# MTRduino_rev5_0.net
KiCad netlist of a schematic drawn in EAGLE
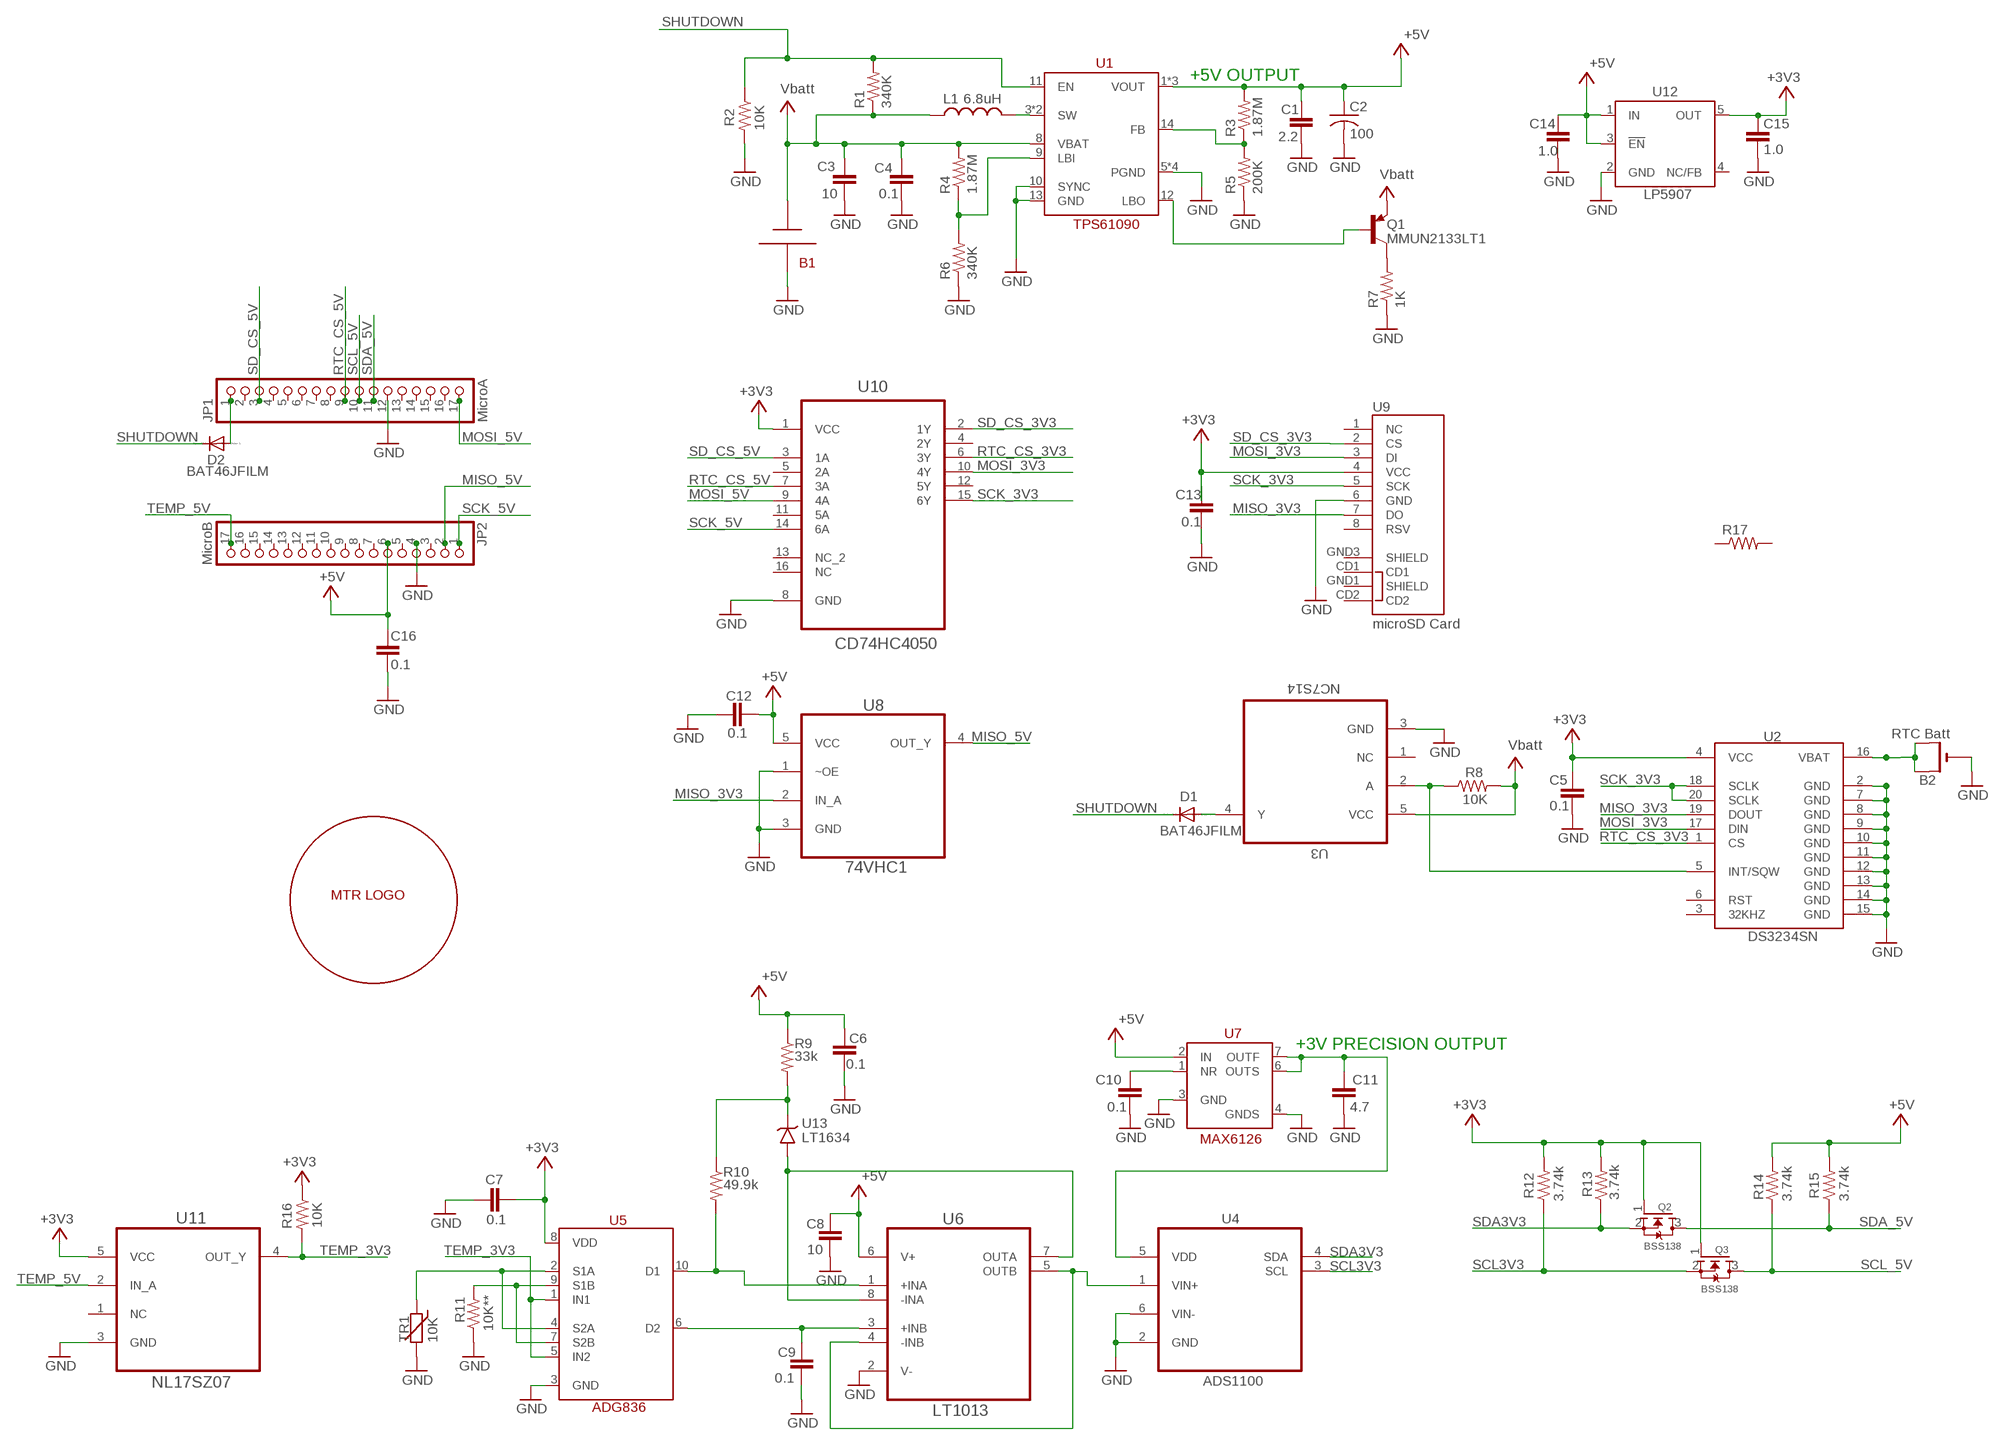
[diagram p0: schematic, sheet 1]

(export (version "E")
  (design (tool "Eeschema 10.0.6"))
  (components
    (comp (ref "B1")
      (value "2x AA BATT")
      (footprint "eagle-import:BATT_AA2")
      (libsource (lib "eagle-import") (part "BATT_AA2"))
    )
    (comp (ref "B2")
      (value "RTC Batt")
      (footprint "eagle-import:CR1220-SMD")
      (libsource (lib "eagle-import") (part "CR1220SMT"))
    )
    (comp (ref "C1")
      (value "2.2")
      (footprint "eagle-import:C0603")
      (libsource (lib "eagle-import") (part "C-EUC0603"))
    )
    (comp (ref "C2")
      (value "100")
      (footprint "eagle-import:C1206K")
      (libsource (lib "eagle-import") (part "C-USC1206K"))
    )
    (comp (ref "C3")
      (value "10")
      (footprint "eagle-import:C0603")
      (libsource (lib "eagle-import") (part "C-EUC0603"))
    )
    (comp (ref "C4")
      (value "0.1")
      (footprint "eagle-import:C0603")
      (libsource (lib "eagle-import") (part "C-EUC0603"))
    )
    (comp (ref "C5")
      (value "0.1")
      (footprint "eagle-import:C0603")
      (libsource (lib "eagle-import") (part "C-EUC0603"))
    )
    (comp (ref "C6")
      (value "0.1")
      (footprint "eagle-import:C0603")
      (libsource (lib "eagle-import") (part "C-EUC0603"))
    )
    (comp (ref "C7")
      (value "0.1")
      (footprint "eagle-import:C0603")
      (libsource (lib "eagle-import") (part "C-EUC0603"))
    )
    (comp (ref "C8")
      (value "10")
      (footprint "eagle-import:C0603")
      (libsource (lib "eagle-import") (part "C-EUC0603"))
    )
    (comp (ref "C9")
      (value "0.1")
      (footprint "eagle-import:C0603")
      (libsource (lib "eagle-import") (part "C-EUC0603"))
    )
    (comp (ref "C10")
      (value "0.1")
      (footprint "eagle-import:C0603")
      (libsource (lib "eagle-import") (part "C-EUC0603"))
    )
    (comp (ref "C11")
      (value "4.7")
      (footprint "eagle-import:C0603")
      (libsource (lib "eagle-import") (part "C-EUC0603"))
    )
    (comp (ref "C12")
      (value "0.1")
      (footprint "eagle-import:C0603")
      (libsource (lib "eagle-import") (part "C-EUC0603"))
    )
    (comp (ref "C13")
      (value "0.1")
      (footprint "eagle-import:C0603")
      (libsource (lib "eagle-import") (part "C-EUC0603"))
    )
    (comp (ref "C14")
      (value "1.0")
      (footprint "eagle-import:C0603")
      (libsource (lib "eagle-import") (part "C-EUC0603"))
    )
    (comp (ref "C15")
      (value "1.0")
      (footprint "eagle-import:C0603")
      (libsource (lib "eagle-import") (part "C-EUC0603"))
    )
    (comp (ref "C16")
      (value "0.1")
      (footprint "eagle-import:C0603")
      (libsource (lib "eagle-import") (part "C-EUC0603"))
    )
    (comp (ref "D1")
      (value "BAT46JFILM")
      (footprint "eagle-import:SOD323-R")
      (libsource (lib "eagle-import") (part "DIODE-SOD323-R"))
    )
    (comp (ref "D2")
      (value "BAT46JFILM")
      (footprint "eagle-import:SOD323-R")
      (libsource (lib "eagle-import") (part "DIODE-SOD323-R"))
    )
    (comp (ref "JP1")
      (value "MicroA")
      (footprint "eagle-import:1X17")
      (libsource (lib "eagle-import") (part "PINHD-1X17"))
    )
    (comp (ref "JP2")
      (value "MicroB")
      (footprint "eagle-import:1X17")
      (libsource (lib "eagle-import") (part "PINHD-1X17"))
    )
    (comp (ref "L1")
      (value "6.8uH")
      (footprint "eagle-import:VLC6045")
      (libsource (lib "eagle-import") (part "L-USVLC6045"))
    )
    (comp (ref "Q1")
      (value "MMUN2133LT1")
      (footprint "eagle-import:SC59-BEC")
      (libsource (lib "eagle-import") (part "MMUN2111LT1"))
    )
    (comp (ref "Q2")
      (value "BSS138")
      (footprint "eagle-import:SOT23")
      (libsource (lib "eagle-import") (part "MOSFET-NREFLOW"))
    )
    (comp (ref "Q3")
      (value "BSS138")
      (footprint "eagle-import:SOT23")
      (libsource (lib "eagle-import") (part "MOSFET-NREFLOW"))
    )
    (comp (ref "R1")
      (value "340K")
      (footprint "eagle-import:R0603")
      (libsource (lib "eagle-import") (part "resistor_R-US_R0603"))
    )
    (comp (ref "R2")
      (value "10K")
      (footprint "eagle-import:R0603")
      (libsource (lib "eagle-import") (part "resistor_R-US_R0603"))
    )
    (comp (ref "R3")
      (value "1.87M")
      (footprint "eagle-import:R0805")
      (libsource (lib "eagle-import") (part "resistor_R-US_R0805"))
    )
    (comp (ref "R4")
      (value "1.87M")
      (footprint "eagle-import:R0805")
      (libsource (lib "eagle-import") (part "resistor_R-US_R0805"))
    )
    (comp (ref "R5")
      (value "200K")
      (footprint "eagle-import:R0603")
      (libsource (lib "eagle-import") (part "resistor_R-US_R0603"))
    )
    (comp (ref "R6")
      (value "340K")
      (footprint "eagle-import:R0603")
      (libsource (lib "eagle-import") (part "resistor_R-US_R0603"))
    )
    (comp (ref "R7")
      (value "1K")
      (footprint "eagle-import:R0603")
      (libsource (lib "eagle-import") (part "resistor_R-US_R0603"))
    )
    (comp (ref "R8")
      (value "10K")
      (footprint "eagle-import:R0603")
      (libsource (lib "eagle-import") (part "resistor_R-US_R0603"))
    )
    (comp (ref "R9")
      (value "33k")
      (footprint "eagle-import:R0603")
      (libsource (lib "eagle-import") (part "resistor_R-US_R0603"))
    )
    (comp (ref "R10")
      (value "49.9k")
      (footprint "eagle-import:R0603")
      (libsource (lib "eagle-import") (part "resistor_R-US_R0603"))
    )
    (comp (ref "R11")
      (value "10K**")
      (footprint "eagle-import:R1206")
      (libsource (lib "eagle-import") (part "R-US_R1206"))
    )
    (comp (ref "R12")
      (value "3.74k")
      (footprint "eagle-import:R0603")
      (libsource (lib "eagle-import") (part "resistor_R-US_R0603"))
    )
    (comp (ref "R13")
      (value "3.74k")
      (footprint "eagle-import:R0603")
      (libsource (lib "eagle-import") (part "resistor_R-US_R0603"))
    )
    (comp (ref "R14")
      (value "3.74k")
      (footprint "eagle-import:R0603")
      (libsource (lib "eagle-import") (part "resistor_R-US_R0603"))
    )
    (comp (ref "R15")
      (value "3.74k")
      (footprint "eagle-import:R0603")
      (libsource (lib "eagle-import") (part "resistor_R-US_R0603"))
    )
    (comp (ref "R16")
      (value "10K")
      (footprint "eagle-import:R0603")
      (libsource (lib "eagle-import") (part "resistor_R-US_R0603"))
    )
    (comp (ref "R17")
      (value "R-US_R0805")
      (footprint "eagle-import:R0805")
      (libsource (lib "eagle-import") (part "resistor_R-US_R0805"))
    )
    (comp (ref "TR1")
      (value "10K")
      (footprint "eagle-import:R-5")
      (libsource (lib "eagle-import") (part "THERMISTOR_R-5"))
    )
    (comp (ref "U$1")
      (value "MTRLOGO")
      (footprint "eagle-import:MTRLOGO")
      (libsource (lib "eagle-import") (part "MTRLOGO"))
    )
    (comp (ref "U1")
      (value "TPS61090")
      (footprint "eagle-import:QFN16-4X4")
      (libsource (lib "eagle-import") (part "TPS61090RSAR"))
    )
    (comp (ref "U2")
      (value "DS3234SN")
      (footprint "eagle-import:DS3234")
      (libsource (lib "eagle-import") (part "DS3234"))
    )
    (comp (ref "U3")
      (value "NC7S14")
      (footprint "eagle-import:SOT95P280X145-5N")
      (fields (field (name "MPN") "1P1G14MDBVREPG4"))
      (libsource (lib "eagle-import") (part "1P1G14MDBVREPG4"))
    )
    (comp (ref "U4")
      (value "ADS1100")
      (footprint "eagle-import:SOT95P280X145-6N")
      (fields (field (name "MPN") "ADS1100A0IDBVT"))
      (libsource (lib "eagle-import") (part "ADS1100A0IDBVT"))
    )
    (comp (ref "U5")
      (value "ADG836")
      (footprint "eagle-import:MSOP10")
      (libsource (lib "eagle-import") (part "ADG836"))
    )
    (comp (ref "U6")
      (value "LT1013")
      (footprint "eagle-import:SOIC127P600X175-8N")
      (fields (field (name "MPN") "LT1013DS8#PBF"))
      (libsource (lib "eagle-import") (part "LT1013DS8PBF"))
    )
    (comp (ref "U7")
      (value "MAX6126")
      (footprint "eagle-import:SOIC127P600X175-8N")
      (libsource (lib "eagle-import") (part "MAX6126"))
    )
    (comp (ref "U8")
      (value "74VHC1")
      (footprint "eagle-import:SOT65P210X110-5N")
      (fields (field (name "MPN") "M74VHC1GT125DF1G"))
      (libsource (lib "eagle-import") (part "M74VHC1GT125DF1G"))
    )
    (comp (ref "U9")
      (value "microSD Card")
      (footprint "eagle-import:MICROSD_1_1")
      (libsource (lib "eagle-import") (part "USD-SOCKET"))
    )
    (comp (ref "U10")
      (value "CD74HC4050")
      (footprint "eagle-import:SOIC127P600X175-16N")
      (fields (field (name "MPN") "M74HC4050RM13TR"))
      (libsource (lib "eagle-import") (part "M74HC4050RM13TR"))
    )
    (comp (ref "U11")
      (value "NL17SZ07")
      (footprint "eagle-import:SOT65P210X110-5N")
      (fields (field (name "MPN") "NL17SZ07DFT2G"))
      (libsource (lib "eagle-import") (part "NL17SZ07DFT2G"))
    )
    (comp (ref "U12")
      (value "LP5907")
      (footprint "eagle-import:SOT23-DBV")
      (fields (field (name "MF") "TEXAS INSTRUMENTS") (field (name "MPN") "TPS77030DBVT"))
      (libsource (lib "eagle-import") (part "TPS77030"))
    )
    (comp (ref "U13")
      (value "LT1634")
      (footprint "eagle-import:S8")
      (libsource (lib "eagle-import") (part "LT1634BIS8-1.25"))
    )
  )
  (nets
    (net (code "1") (name "+3V3") (class "Default")
      (node (ref "C13") (pin "1") (pinfunction "1_1") (pintype "passive"))
      (node (ref "C15") (pin "1") (pinfunction "1_1") (pintype "passive"))
      (node (ref "C5") (pin "1") (pinfunction "1_1") (pintype "passive"))
      (node (ref "C7") (pin "2") (pinfunction "2_2") (pintype "passive"))
      (node (ref "Q2") (pin "1") (pinfunction "G_1") (pintype "bidirectional"))
      (node (ref "Q3") (pin "1") (pinfunction "G_1") (pintype "bidirectional"))
      (node (ref "R12") (pin "2") (pinfunction "2_2") (pintype "passive"))
      (node (ref "R13") (pin "2") (pinfunction "2_2") (pintype "passive"))
      (node (ref "R16") (pin "1") (pinfunction "1_1") (pintype "passive"))
      (node (ref "U10") (pin "1") (pinfunction "VCC_1") (pintype "power_in"))
      (node (ref "U11") (pin "5") (pinfunction "VCC_5") (pintype "power_in"))
      (node (ref "U12") (pin "5") (pinfunction "OUT_5") (pintype "passive"))
      (node (ref "U2") (pin "4") (pinfunction "VCC_4") (pintype "bidirectional"))
      (node (ref "U5") (pin "8") (pinfunction "VDD_8") (pintype "bidirectional"))
      (node (ref "U9") (pin "4") (pinfunction "VCC_4") (pintype "bidirectional"))
    )
    (net (code "2") (name "+5V") (class "Default")
      (node (ref "C1") (pin "1") (pinfunction "1_1") (pintype "passive"))
      (node (ref "C12") (pin "1") (pinfunction "1_1") (pintype "passive"))
      (node (ref "C14") (pin "1") (pinfunction "1_1") (pintype "passive"))
      (node (ref "C16") (pin "1") (pinfunction "1_1") (pintype "passive"))
      (node (ref "C2") (pin "1") (pinfunction "1_1") (pintype "passive"))
      (node (ref "C6") (pin "2") (pinfunction "2_2") (pintype "passive"))
      (node (ref "C8") (pin "2") (pinfunction "2_2") (pintype "passive"))
      (node (ref "JP2") (pin "6") (pinfunction "6_6") (pintype "passive"))
      (node (ref "R14") (pin "2") (pinfunction "2_2") (pintype "passive"))
      (node (ref "R15") (pin "2") (pinfunction "2_2") (pintype "passive"))
      (node (ref "R3") (pin "2") (pinfunction "2_2") (pintype "passive"))
      (node (ref "R9") (pin "1") (pinfunction "1_1") (pintype "passive"))
      (node (ref "U1") (pin "1") (pinfunction "VOUT_1") (pintype "bidirectional"))
      (node (ref "U1") (pin "15") (pinfunction "VOUT_15") (pintype "bidirectional"))
      (node (ref "U1") (pin "16") (pinfunction "VOUT_16") (pintype "bidirectional"))
      (node (ref "U12") (pin "1") (pinfunction "IN_1") (pintype "input"))
      (node (ref "U12") (pin "3") (pinfunction "~{EN}_3") (pintype "input"))
      (node (ref "U6") (pin "6") (pinfunction "V+_6") (pintype "power_in"))
      (node (ref "U7") (pin "2") (pinfunction "IN_2") (pintype "input"))
      (node (ref "U8") (pin "5") (pinfunction "VCC_5") (pintype "power_in"))
    )
    (net (code "3") (name "/MISO_3V3") (class "Default")
      (node (ref "U2") (pin "19") (pinfunction "DOUT_19") (pintype "bidirectional"))
      (node (ref "U8") (pin "2") (pinfunction "IN_A_2") (pintype "input"))
      (node (ref "U9") (pin "7") (pinfunction "DO_7") (pintype "bidirectional"))
    )
    (net (code "4") (name "/MISO_5V") (class "Default")
      (node (ref "JP2") (pin "2") (pinfunction "2_2") (pintype "passive"))
      (node (ref "U8") (pin "4") (pinfunction "OUT_Y_4") (pintype "output"))
    )
    (net (code "5") (name "/MOSI_3V3") (class "Default")
      (node (ref "U10") (pin "10") (pinfunction "4Y_10") (pintype "output"))
      (node (ref "U2") (pin "17") (pinfunction "DIN_17") (pintype "bidirectional"))
      (node (ref "U9") (pin "3") (pinfunction "DI_3") (pintype "bidirectional"))
    )
    (net (code "6") (name "/MOSI_5V") (class "Default")
      (node (ref "JP1") (pin "17") (pinfunction "17_17") (pintype "passive"))
      (node (ref "U10") (pin "9") (pinfunction "4A_9") (pintype "input"))
    )
    (net (code "7") (name "/RTC_CS_3V3") (class "Default")
      (node (ref "U10") (pin "6") (pinfunction "3Y_6") (pintype "output"))
      (node (ref "U2") (pin "1") (pinfunction "CS_1") (pintype "bidirectional"))
    )
    (net (code "8") (name "/RTC_CS_5V") (class "Default")
      (node (ref "JP1") (pin "9") (pinfunction "9_9") (pintype "passive"))
      (node (ref "U10") (pin "7") (pinfunction "3A_7") (pintype "input"))
    )
    (net (code "9") (name "/SCK_3V3") (class "Default")
      (node (ref "U10") (pin "15") (pinfunction "6Y_15") (pintype "output"))
      (node (ref "U2") (pin "18") (pinfunction "SCLK_18") (pintype "bidirectional"))
      (node (ref "U2") (pin "20") (pinfunction "SCLK_20") (pintype "bidirectional"))
      (node (ref "U9") (pin "5") (pinfunction "SCK_5") (pintype "bidirectional"))
    )
    (net (code "10") (name "/SCK_5V") (class "Default")
      (node (ref "JP2") (pin "1") (pinfunction "1_1") (pintype "passive"))
      (node (ref "U10") (pin "14") (pinfunction "6A_14") (pintype "input"))
    )
    (net (code "11") (name "/SCL3V3") (class "Default")
      (node (ref "Q3") (pin "2") (pinfunction "S_2") (pintype "bidirectional"))
      (node (ref "R12") (pin "1") (pinfunction "1_1") (pintype "passive"))
      (node (ref "U4") (pin "3") (pinfunction "SCL_3") (pintype "output"))
    )
    (net (code "12") (name "/SCL_5V") (class "Default")
      (node (ref "JP1") (pin "10") (pinfunction "10_10") (pintype "passive"))
      (node (ref "Q3") (pin "3") (pinfunction "D_3") (pintype "bidirectional"))
      (node (ref "R14") (pin "1") (pinfunction "1_1") (pintype "passive"))
    )
    (net (code "13") (name "/SDA3V3") (class "Default")
      (node (ref "Q2") (pin "2") (pinfunction "S_2") (pintype "bidirectional"))
      (node (ref "R13") (pin "1") (pinfunction "1_1") (pintype "passive"))
      (node (ref "U4") (pin "4") (pinfunction "SDA_4") (pintype "output"))
    )
    (net (code "14") (name "/SDA_5V") (class "Default")
      (node (ref "JP1") (pin "11") (pinfunction "11_11") (pintype "passive"))
      (node (ref "Q2") (pin "3") (pinfunction "D_3") (pintype "bidirectional"))
      (node (ref "R15") (pin "1") (pinfunction "1_1") (pintype "passive"))
    )
    (net (code "15") (name "/SD_CS_3V3") (class "Default")
      (node (ref "U10") (pin "2") (pinfunction "1Y_2") (pintype "output"))
      (node (ref "U9") (pin "2") (pinfunction "CS_2") (pintype "bidirectional"))
    )
    (net (code "16") (name "/SD_CS_5V") (class "Default")
      (node (ref "JP1") (pin "3") (pinfunction "3_3") (pintype "passive"))
      (node (ref "U10") (pin "3") (pinfunction "1A_3") (pintype "input"))
    )
    (net (code "17") (name "/SHUTDOWN") (class "Default")
      (node (ref "D1") (pin "C") (pinfunction "C_C") (pintype "passive"))
      (node (ref "D2") (pin "C") (pinfunction "C_C") (pintype "passive"))
      (node (ref "R1") (pin "2") (pinfunction "2_2") (pintype "passive"))
      (node (ref "R2") (pin "1") (pinfunction "1_1") (pintype "passive"))
      (node (ref "U1") (pin "11") (pinfunction "EN_11") (pintype "bidirectional"))
    )
    (net (code "18") (name "/TEMP_3V3") (class "Default")
      (node (ref "R16") (pin "2") (pinfunction "2_2") (pintype "passive"))
      (node (ref "U11") (pin "4") (pinfunction "OUT_Y_4") (pintype "output"))
      (node (ref "U5") (pin "1") (pinfunction "IN1_1") (pintype "bidirectional"))
      (node (ref "U5") (pin "5") (pinfunction "IN2_5") (pintype "bidirectional"))
    )
    (net (code "19") (name "/TEMP_5V") (class "Default")
      (node (ref "JP2") (pin "17") (pinfunction "17_17") (pintype "passive"))
      (node (ref "U11") (pin "2") (pinfunction "IN_A_2") (pintype "input"))
    )
    (net (code "20") (name "GND") (class "Default")
      (node (ref "B1") (pin "-") (pinfunction "+_-") (pintype "bidirectional"))
      (node (ref "B2") (pin "-") (pinfunction "-_-") (pintype "passive"))
      (node (ref "C1") (pin "2") (pinfunction "2_2") (pintype "passive"))
      (node (ref "C10") (pin "2") (pinfunction "2_2") (pintype "passive"))
      (node (ref "C11") (pin "2") (pinfunction "2_2") (pintype "passive"))
      (node (ref "C12") (pin "2") (pinfunction "2_2") (pintype "passive"))
      (node (ref "C13") (pin "2") (pinfunction "2_2") (pintype "passive"))
      (node (ref "C14") (pin "2") (pinfunction "2_2") (pintype "passive"))
      (node (ref "C15") (pin "2") (pinfunction "2_2") (pintype "passive"))
      (node (ref "C16") (pin "2") (pinfunction "2_2") (pintype "passive"))
      (node (ref "C2") (pin "2") (pinfunction "2_2") (pintype "passive"))
      (node (ref "C3") (pin "2") (pinfunction "2_2") (pintype "passive"))
      (node (ref "C4") (pin "2") (pinfunction "2_2") (pintype "passive"))
      (node (ref "C5") (pin "2") (pinfunction "2_2") (pintype "passive"))
      (node (ref "C6") (pin "1") (pinfunction "1_1") (pintype "passive"))
      (node (ref "C7") (pin "1") (pinfunction "1_1") (pintype "passive"))
      (node (ref "C8") (pin "1") (pinfunction "1_1") (pintype "passive"))
      (node (ref "C9") (pin "1") (pinfunction "1_1") (pintype "passive"))
      (node (ref "JP1") (pin "12") (pinfunction "12_12") (pintype "passive"))
      (node (ref "JP2") (pin "4") (pinfunction "4_4") (pintype "passive"))
      (node (ref "R11") (pin "1") (pinfunction "1_1") (pintype "passive"))
      (node (ref "R2") (pin "2") (pinfunction "2_2") (pintype "passive"))
      (node (ref "R5") (pin "1") (pinfunction "1_1") (pintype "passive"))
      (node (ref "R6") (pin "1") (pinfunction "1_1") (pintype "passive"))
      (node (ref "R7") (pin "1") (pinfunction "1_1") (pintype "passive"))
      (node (ref "TR1") (pin "2") (pinfunction "2_2") (pintype "passive"))
      (node (ref "U1") (pin "10") (pinfunction "SYNC_10") (pintype "bidirectional"))
      (node (ref "U1") (pin "13") (pinfunction "GND_13") (pintype "bidirectional"))
      (node (ref "U1") (pin "5") (pinfunction "PGND_5") (pintype "bidirectional"))
      (node (ref "U1") (pin "6") (pinfunction "PGND_6") (pintype "bidirectional"))
      (node (ref "U1") (pin "7") (pinfunction "PGND_7") (pintype "bidirectional"))
      (node (ref "U1") (pin "EXP") (pinfunction "PGND_EXP") (pintype "bidirectional"))
      (node (ref "U10") (pin "8") (pinfunction "GND_8") (pintype "passive"))
      (node (ref "U11") (pin "3") (pinfunction "GND_3") (pintype "passive"))
      (node (ref "U12") (pin "2") (pinfunction "GND_2") (pintype "power_in"))
      (node (ref "U2") (pin "10") (pinfunction "GND_10") (pintype "bidirectional"))
      (node (ref "U2") (pin "11") (pinfunction "GND_11") (pintype "bidirectional"))
      (node (ref "U2") (pin "12") (pinfunction "GND_12") (pintype "bidirectional"))
      (node (ref "U2") (pin "13") (pinfunction "GND_13") (pintype "bidirectional"))
      (node (ref "U2") (pin "14") (pinfunction "GND_14") (pintype "bidirectional"))
      (node (ref "U2") (pin "15") (pinfunction "GND_15") (pintype "bidirectional"))
      (node (ref "U2") (pin "2") (pinfunction "GND_2") (pintype "bidirectional"))
      (node (ref "U2") (pin "7") (pinfunction "GND_7") (pintype "bidirectional"))
      (node (ref "U2") (pin "8") (pinfunction "GND_8") (pintype "bidirectional"))
      (node (ref "U2") (pin "9") (pinfunction "GND_9") (pintype "bidirectional"))
      (node (ref "U3") (pin "3") (pinfunction "GND_3") (pintype "passive"))
      (node (ref "U4") (pin "2") (pinfunction "GND_2") (pintype "passive"))
      (node (ref "U4") (pin "6") (pinfunction "VIN-_6") (pintype "input"))
      (node (ref "U5") (pin "3") (pinfunction "GND_3") (pintype "bidirectional"))
      (node (ref "U6") (pin "2") (pinfunction "V-_2") (pintype "power_in"))
      (node (ref "U7") (pin "3") (pinfunction "GND_3") (pintype "input"))
      (node (ref "U7") (pin "4") (pinfunction "GNDS_4") (pintype "input"))
      (node (ref "U8") (pin "1") (pinfunction "~{OE}_1") (pintype "input"))
      (node (ref "U8") (pin "3") (pinfunction "GND_3") (pintype "passive"))
      (node (ref "U9") (pin "6") (pinfunction "GND_6") (pintype "bidirectional"))
    )
    (net (code "21") (name "Net-(B2-+)") (class "Default")
      (node (ref "B2") (pin "+$1") (pinfunction "+_+$1") (pintype "passive"))
      (node (ref "B2") (pin "+$2") (pinfunction "+1_+$2") (pintype "passive"))
      (node (ref "U2") (pin "16") (pinfunction "VBAT_16") (pintype "bidirectional"))
    )
    (net (code "22") (name "Net-(D2-PadA)") (class "Default")
      (node (ref "D2") (pin "A") (pinfunction "A_A") (pintype "passive"))
      (node (ref "JP1") (pin "1") (pinfunction "1_1") (pintype "passive"))
    )
    (net (code "23") (name "Net-(L1-2)") (class "Default")
      (node (ref "L1") (pin "P$3") (pinfunction "2_P$3") (pintype "passive"))
      (node (ref "U1") (pin "3") (pinfunction "SW_3") (pintype "bidirectional"))
      (node (ref "U1") (pin "4") (pinfunction "SW_4") (pintype "bidirectional"))
    )
    (net (code "24") (name "Net-(Q1-PadC)") (class "Default")
      (node (ref "Q1") (pin "C") (pinfunction "C_C") (pintype "passive"))
      (node (ref "R7") (pin "2") (pinfunction "2_2") (pintype "passive"))
    )
    (net (code "25") (name "Net-(U1-FB)") (class "Default")
      (node (ref "R3") (pin "1") (pinfunction "1_1") (pintype "passive"))
      (node (ref "R5") (pin "2") (pinfunction "2_2") (pintype "passive"))
      (node (ref "U1") (pin "14") (pinfunction "FB_14") (pintype "bidirectional"))
    )
    (net (code "26") (name "Net-(U1-LBI)") (class "Default")
      (node (ref "R4") (pin "1") (pinfunction "1_1") (pintype "passive"))
      (node (ref "R6") (pin "2") (pinfunction "2_2") (pintype "passive"))
      (node (ref "U1") (pin "9") (pinfunction "LBI_9") (pintype "bidirectional"))
    )
    (net (code "27") (name "Net-(U1-LBO)") (class "Default")
      (node (ref "Q1") (pin "B") (pinfunction "B_B") (pintype "passive"))
      (node (ref "U1") (pin "12") (pinfunction "LBO_12") (pintype "bidirectional"))
    )
    (net (code "28") (name "Net-(U2-INT{slash}SQW)") (class "Default")
      (node (ref "R8") (pin "1") (pinfunction "1_1") (pintype "passive"))
      (node (ref "U2") (pin "5") (pinfunction "INT/SQW_5") (pintype "bidirectional"))
      (node (ref "U3") (pin "2") (pinfunction "A_2") (pintype "input"))
    )
    (net (code "29") (name "Net-(U3-Y)") (class "Default")
      (node (ref "D1") (pin "A") (pinfunction "A_A") (pintype "passive"))
      (node (ref "U3") (pin "4") (pinfunction "Y_4") (pintype "output"))
    )
    (net (code "30") (name "Net-(U4-VDD)") (class "Default")
      (node (ref "C11") (pin "1") (pinfunction "1_1") (pintype "passive"))
      (node (ref "U4") (pin "5") (pinfunction "VDD_5") (pintype "power_in"))
      (node (ref "U7") (pin "6") (pinfunction "OUTS_6") (pintype "output"))
      (node (ref "U7") (pin "7") (pinfunction "OUTF_7") (pintype "output"))
    )
    (net (code "31") (name "Net-(U4-VIN+)") (class "Default")
      (node (ref "U4") (pin "1") (pinfunction "VIN+_1") (pintype "input"))
      (node (ref "U6") (pin "4") (pinfunction "-INB_4") (pintype "input"))
      (node (ref "U6") (pin "5") (pinfunction "OUTB_5") (pintype "output"))
    )
    (net (code "32") (name "Net-(U5-D1)") (class "Default")
      (node (ref "R10") (pin "2") (pinfunction "2_2") (pintype "passive"))
      (node (ref "U5") (pin "10") (pinfunction "D1_10") (pintype "bidirectional"))
      (node (ref "U6") (pin "1") (pinfunction "+INA_1") (pintype "input"))
    )
    (net (code "33") (name "Net-(U5-D2)") (class "Default")
      (node (ref "C9") (pin "2") (pinfunction "2_2") (pintype "passive"))
      (node (ref "U5") (pin "6") (pinfunction "D2_6") (pintype "bidirectional"))
      (node (ref "U6") (pin "3") (pinfunction "+INB_3") (pintype "input"))
    )
    (net (code "34") (name "Net-(U5-S1A)") (class "Default")
      (node (ref "TR1") (pin "1") (pinfunction "1_1") (pintype "passive"))
      (node (ref "U5") (pin "2") (pinfunction "S1A_2") (pintype "bidirectional"))
      (node (ref "U5") (pin "4") (pinfunction "S2A_4") (pintype "bidirectional"))
    )
    (net (code "35") (name "Net-(U5-S1B)") (class "Default")
      (node (ref "R11") (pin "2") (pinfunction "2_2") (pintype "passive"))
      (node (ref "U5") (pin "7") (pinfunction "S2B_7") (pintype "bidirectional"))
      (node (ref "U5") (pin "9") (pinfunction "S1B_9") (pintype "bidirectional"))
    )
    (net (code "36") (name "Net-(U7-NR)") (class "Default")
      (node (ref "C10") (pin "1") (pinfunction "1_1") (pintype "passive"))
      (node (ref "U7") (pin "1") (pinfunction "NR_1") (pintype "bidirectional"))
    )
    (net (code "37") (name "Net-(U13-GND)") (class "Default")
      (node (ref "U13") (pin "4") (pinfunction "GND_4") (pintype "passive"))
      (node (ref "U6") (pin "7") (pinfunction "OUTA_7") (pintype "output"))
      (node (ref "U6") (pin "8") (pinfunction "-INA_8") (pintype "input"))
    )
    (net (code "38") (name "Net-(U13-VOUT)") (class "Default")
      (node (ref "R10") (pin "1") (pinfunction "1_1") (pintype "passive"))
      (node (ref "R9") (pin "2") (pinfunction "2_2") (pintype "passive"))
      (node (ref "U13") (pin "6") (pinfunction "VOUT_6") (pintype "passive"))
    )
    (net (code "39") (name "Vbatt") (class "Default")
      (node (ref "B1") (pin "+") (pinfunction "-_+") (pintype "bidirectional"))
      (node (ref "C3") (pin "1") (pinfunction "1_1") (pintype "passive"))
      (node (ref "C4") (pin "1") (pinfunction "1_1") (pintype "passive"))
      (node (ref "L1") (pin "P$2") (pinfunction "1_P$2") (pintype "passive"))
      (node (ref "Q1") (pin "E") (pinfunction "E_E") (pintype "passive"))
      (node (ref "R1") (pin "1") (pinfunction "1_1") (pintype "passive"))
      (node (ref "R4") (pin "2") (pinfunction "2_2") (pintype "passive"))
      (node (ref "R8") (pin "2") (pinfunction "2_2") (pintype "passive"))
      (node (ref "U1") (pin "8") (pinfunction "VBAT_8") (pintype "bidirectional"))
      (node (ref "U3") (pin "5") (pinfunction "VCC_5") (pintype "power_in"))
    )
    (net (code "40") (name "unconnected-(JP1-Pad2)") (class "Default")
      (node (ref "JP1") (pin "2") (pinfunction "2_2") (pintype "passive"))
    )
    (net (code "41") (name "unconnected-(JP1-Pad4)") (class "Default")
      (node (ref "JP1") (pin "4") (pinfunction "4_4") (pintype "passive"))
    )
    (net (code "42") (name "unconnected-(JP1-Pad5)") (class "Default")
      (node (ref "JP1") (pin "5") (pinfunction "5_5") (pintype "passive"))
    )
    (net (code "43") (name "unconnected-(JP1-Pad6)") (class "Default")
      (node (ref "JP1") (pin "6") (pinfunction "6_6") (pintype "passive"))
    )
    (net (code "44") (name "unconnected-(JP1-Pad7)") (class "Default")
      (node (ref "JP1") (pin "7") (pinfunction "7_7") (pintype "passive"))
    )
    (net (code "45") (name "unconnected-(JP1-Pad8)") (class "Default")
      (node (ref "JP1") (pin "8") (pinfunction "8_8") (pintype "passive"))
    )
    (net (code "46") (name "unconnected-(JP1-Pad13)") (class "Default")
      (node (ref "JP1") (pin "13") (pinfunction "13_13") (pintype "passive"))
    )
    (net (code "47") (name "unconnected-(JP1-Pad14)") (class "Default")
      (node (ref "JP1") (pin "14") (pinfunction "14_14") (pintype "passive"))
    )
    (net (code "48") (name "unconnected-(JP1-Pad15)") (class "Default")
      (node (ref "JP1") (pin "15") (pinfunction "15_15") (pintype "passive"))
    )
    (net (code "49") (name "unconnected-(JP1-Pad16)") (class "Default")
      (node (ref "JP1") (pin "16") (pinfunction "16_16") (pintype "passive"))
    )
    (net (code "50") (name "unconnected-(JP2-Pad3)") (class "Default")
      (node (ref "JP2") (pin "3") (pinfunction "3_3") (pintype "passive"))
    )
    (net (code "51") (name "unconnected-(JP2-Pad5)") (class "Default")
      (node (ref "JP2") (pin "5") (pinfunction "5_5") (pintype "passive"))
    )
    (net (code "52") (name "unconnected-(JP2-Pad7)") (class "Default")
      (node (ref "JP2") (pin "7") (pinfunction "7_7") (pintype "passive"))
    )
    (net (code "53") (name "unconnected-(JP2-Pad8)") (class "Default")
      (node (ref "JP2") (pin "8") (pinfunction "8_8") (pintype "passive"))
    )
    (net (code "54") (name "unconnected-(JP2-Pad9)") (class "Default")
      (node (ref "JP2") (pin "9") (pinfunction "9_9") (pintype "passive"))
    )
    (net (code "55") (name "unconnected-(JP2-Pad10)") (class "Default")
      (node (ref "JP2") (pin "10") (pinfunction "10_10") (pintype "passive"))
    )
    (net (code "56") (name "unconnected-(JP2-Pad11)") (class "Default")
      (node (ref "JP2") (pin "11") (pinfunction "11_11") (pintype "passive"))
    )
    (net (code "57") (name "unconnected-(JP2-Pad12)") (class "Default")
      (node (ref "JP2") (pin "12") (pinfunction "12_12") (pintype "passive"))
    )
    (net (code "58") (name "unconnected-(JP2-Pad13)") (class "Default")
      (node (ref "JP2") (pin "13") (pinfunction "13_13") (pintype "passive"))
    )
    (net (code "59") (name "unconnected-(JP2-Pad14)") (class "Default")
      (node (ref "JP2") (pin "14") (pinfunction "14_14") (pintype "passive"))
    )
    (net (code "60") (name "unconnected-(JP2-Pad15)") (class "Default")
      (node (ref "JP2") (pin "15") (pinfunction "15_15") (pintype "passive"))
    )
    (net (code "61") (name "unconnected-(JP2-Pad16)") (class "Default")
      (node (ref "JP2") (pin "16") (pinfunction "16_16") (pintype "passive"))
    )
    (net (code "62") (name "unconnected-(R17-Pad1)") (class "Default")
      (node (ref "R17") (pin "1") (pinfunction "1_1") (pintype "passive"))
    )
    (net (code "63") (name "unconnected-(R17-Pad2)") (class "Default")
      (node (ref "R17") (pin "2") (pinfunction "2_2") (pintype "passive"))
    )
    (net (code "64") (name "unconnected-(U2-32KHZ-Pad3)") (class "Default")
      (node (ref "U2") (pin "3") (pinfunction "32KHZ_3") (pintype "bidirectional"))
    )
    (net (code "65") (name "unconnected-(U2-RST-Pad6)") (class "Default")
      (node (ref "U2") (pin "6") (pinfunction "RST_6") (pintype "bidirectional"))
    )
    (net (code "66") (name "unconnected-(U3-NC-Pad1)") (class "Default")
      (node (ref "U3") (pin "1") (pinfunction "NC_1") (pintype "no_connect"))
    )
    (net (code "67") (name "unconnected-(U9-NC-Pad1)") (class "Default")
      (node (ref "U9") (pin "1") (pinfunction "NC_1") (pintype "bidirectional"))
    )
    (net (code "68") (name "unconnected-(U9-PadCD1)") (class "Default")
      (node (ref "U9") (pin "CD1") (pinfunction "CD1_CD1") (pintype "bidirectional"))
    )
    (net (code "69") (name "unconnected-(U9-PadCD2)") (class "Default")
      (node (ref "U9") (pin "CD2") (pinfunction "CD2_CD2") (pintype "bidirectional"))
    )
    (net (code "70") (name "unconnected-(U9-RSV-Pad8)") (class "Default")
      (node (ref "U9") (pin "8") (pinfunction "RSV_8") (pintype "bidirectional"))
    )
    (net (code "71") (name "unconnected-(U9-SHIELD-PadGND1)") (class "Default")
      (node (ref "U9") (pin "GND1") (pinfunction "SHIELD_GND1") (pintype "bidirectional"))
    )
    (net (code "72") (name "unconnected-(U9-SHIELD-PadGND3)") (class "Default")
      (node (ref "U9") (pin "GND3") (pinfunction "SHIELD_GND3") (pintype "bidirectional"))
    )
    (net (code "73") (name "unconnected-(U10-2A-Pad5)") (class "Default")
      (node (ref "U10") (pin "5") (pinfunction "2A_5") (pintype "input"))
    )
    (net (code "74") (name "unconnected-(U10-2Y-Pad4)") (class "Default")
      (node (ref "U10") (pin "4") (pinfunction "2Y_4") (pintype "output"))
    )
    (net (code "75") (name "unconnected-(U10-5A-Pad11)") (class "Default")
      (node (ref "U10") (pin "11") (pinfunction "5A_11") (pintype "input"))
    )
    (net (code "76") (name "unconnected-(U10-5Y-Pad12)") (class "Default")
      (node (ref "U10") (pin "12") (pinfunction "5Y_12") (pintype "output"))
    )
    (net (code "77") (name "unconnected-(U10-NC-Pad16)") (class "Default")
      (node (ref "U10") (pin "16") (pinfunction "NC_16") (pintype "no_connect"))
    )
    (net (code "78") (name "unconnected-(U10-NC_2-Pad13)") (class "Default")
      (node (ref "U10") (pin "13") (pinfunction "NC_2_13") (pintype "no_connect"))
    )
    (net (code "79") (name "unconnected-(U11-NC-Pad1)") (class "Default")
      (node (ref "U11") (pin "1") (pinfunction "NC_1") (pintype "no_connect"))
    )
    (net (code "80") (name "unconnected-(U12-NC{slash}FB-Pad4)") (class "Default")
      (node (ref "U12") (pin "4") (pinfunction "NC/FB_4") (pintype "passive"))
    )
  )
)
